# PWM.net
KiCad netlist of a schematic drawn in Altium Designer
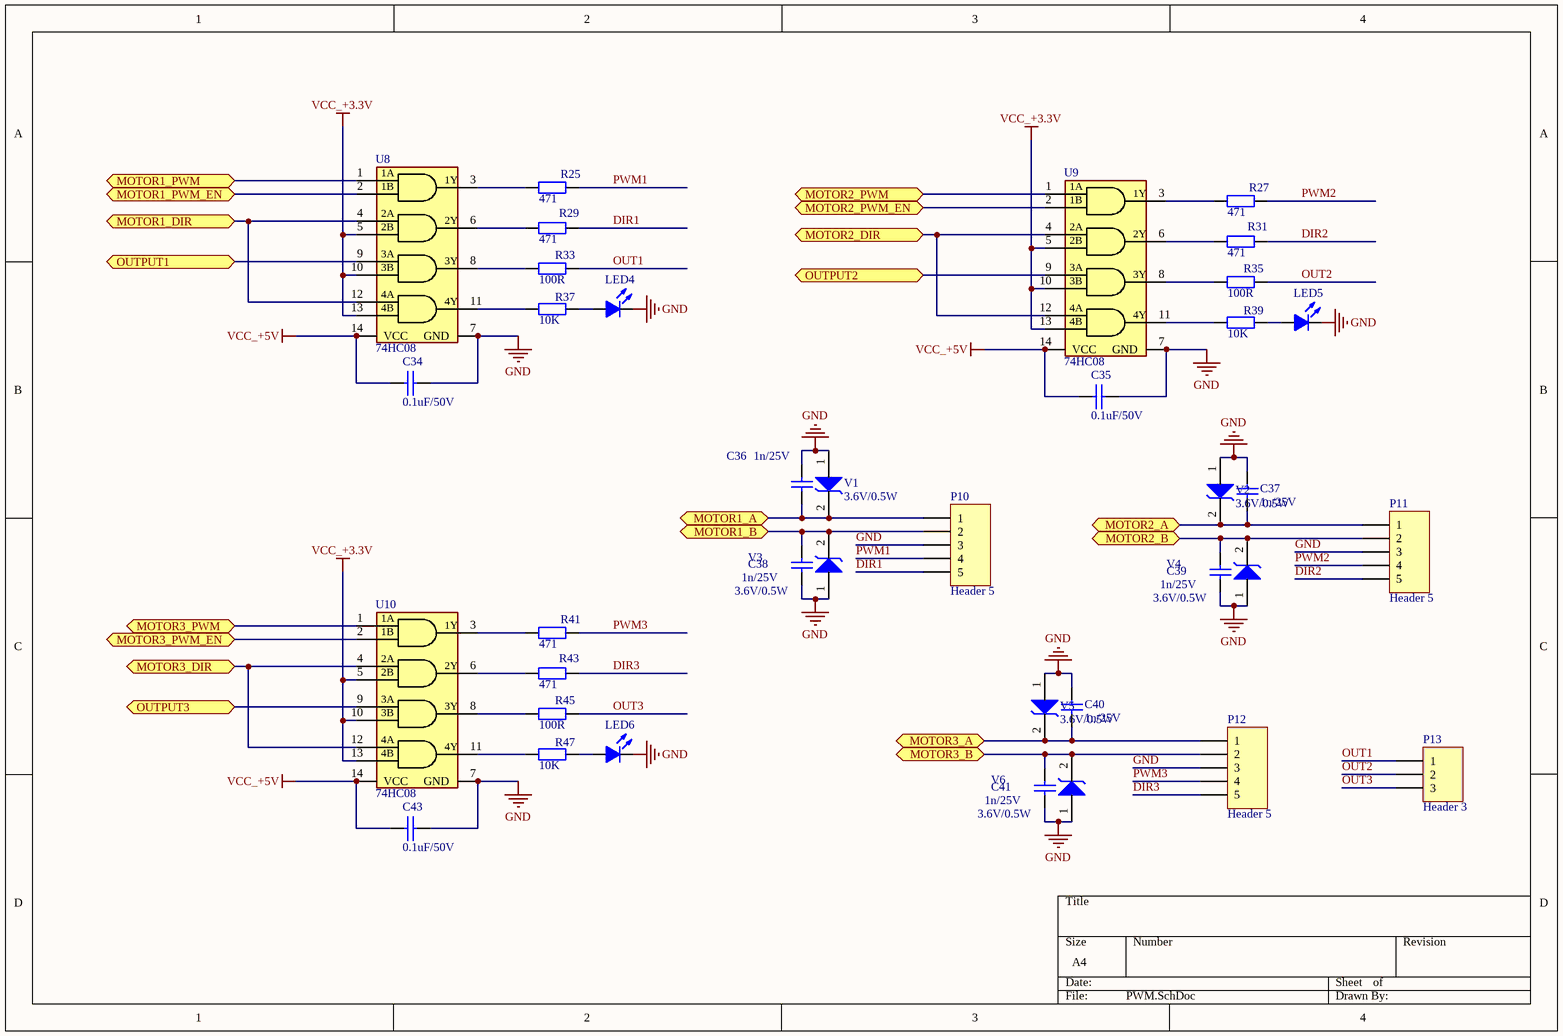
[diagram p0: PWM.SchDoc]

(export (version "E")
  (design (tool "Eeschema 10.0.6"))
  (components
    (comp (ref "C34") (value "0.1uF/50V") (footprint "0603C") (libsource (lib "*") (part "0603C")))
    (comp (ref "C35") (value "0.1uF/50V") (footprint "0603C") (libsource (lib "*") (part "0603C")))
    (comp (ref "C36")
      (value "1n/25V")
      (footprint "0603C")
      (description "Capacitor")
      (libsource (lib "*") (part "Cap"))
    )
    (comp (ref "C37")
      (value "1n/25V")
      (footprint "0603C")
      (description "Capacitor")
      (libsource (lib "*") (part "Cap"))
    )
    (comp (ref "C38")
      (value "1n/25V")
      (footprint "0603C")
      (description "Capacitor")
      (libsource (lib "*") (part "Cap"))
    )
    (comp (ref "C39")
      (value "1n/25V")
      (footprint "0603C")
      (description "Capacitor")
      (libsource (lib "*") (part "Cap"))
    )
    (comp (ref "C40")
      (value "1n/25V")
      (footprint "0603C")
      (description "Capacitor")
      (libsource (lib "*") (part "Cap"))
    )
    (comp (ref "C41")
      (value "1n/25V")
      (footprint "0603C")
      (description "Capacitor")
      (libsource (lib "*") (part "Cap"))
    )
    (comp (ref "C43") (value "0.1uF/50V") (footprint "0603C") (libsource (lib "*") (part "0603C")))
    (comp (ref "LED4")
      (value "LED")
      (footprint "LED-0603")
      (description "Typical INFRARED GaAs LED")
      (fields (field (name "PUBLISHER") "Altium Limited"))
      (libsource (lib "Calf") (part "LED"))
    )
    (comp (ref "LED5")
      (value "LED")
      (footprint "LED-0603")
      (description "Typical INFRARED GaAs LED")
      (fields (field (name "PUBLISHER") "Altium Limited"))
      (libsource (lib "Calf") (part "LED"))
    )
    (comp (ref "LED6")
      (value "LED")
      (footprint "LED-0603")
      (description "Typical INFRARED GaAs LED")
      (fields (field (name "PUBLISHER") "Altium Limited"))
      (libsource (lib "Calf") (part "LED"))
    )
    (comp (ref "P10")
      (value "Header 5")
      (footprint "HT396")
      (description "Header, 5-Pin")
      (fields (field (name "PUBLISHER") "Altium Limited"))
      (libsource (lib "Miscellaneous Connectors") (part "Header 5"))
    )
    (comp (ref "P11")
      (value "Header 5")
      (footprint "HT396")
      (description "Header, 5-Pin")
      (fields (field (name "PUBLISHER") "Altium Limited"))
      (libsource (lib "Miscellaneous Connectors") (part "Header 5"))
    )
    (comp (ref "P12")
      (value "Header 5")
      (footprint "HT396")
      (description "Header, 5-Pin")
      (fields (field (name "PUBLISHER") "Altium Limited"))
      (libsource (lib "Miscellaneous Connectors") (part "Header 5"))
    )
    (comp (ref "P13")
      (value "Header 3")
      (footprint "HT396  3P")
      (description "Header, 3-Pin")
      (fields (field (name "PUBLISHER") "Altium Limited"))
      (libsource (lib "Miscellaneous Connectors") (part "Header 3"))
    )
    (comp (ref "R25") (value "471") (footprint "0603R") (libsource (lib "*") (part "0603R")))
    (comp (ref "R27") (value "471") (footprint "0603R") (libsource (lib "*") (part "0603R")))
    (comp (ref "R29") (value "471") (footprint "0603R") (libsource (lib "*") (part "0603R")))
    (comp (ref "R31") (value "471") (footprint "0603R") (libsource (lib "*") (part "0603R")))
    (comp (ref "R33") (value "100R") (footprint "0603R") (libsource (lib "*") (part "0603R")))
    (comp (ref "R35") (value "100R") (footprint "0603R") (libsource (lib "*") (part "0603R")))
    (comp (ref "R37") (value "10K") (footprint "0603R") (libsource (lib "*") (part "0603R")))
    (comp (ref "R39") (value "10K") (footprint "0603R") (libsource (lib "*") (part "0603R")))
    (comp (ref "R41") (value "471") (footprint "0603R") (libsource (lib "*") (part "0603R")))
    (comp (ref "R43") (value "471") (footprint "0603R") (libsource (lib "*") (part "0603R")))
    (comp (ref "R45") (value "100R") (footprint "0603R") (libsource (lib "*") (part "0603R")))
    (comp (ref "R47") (value "10K") (footprint "0603R") (libsource (lib "*") (part "0603R")))
    (comp (ref "U8")
      (value "74HC08")
      (footprint "SOP14")
      (description "Quad 2-input NAND gate")
      (libsource (lib "Schlib") (part "74HC08"))
    )
    (comp (ref "U9")
      (value "74HC08")
      (footprint "SOP14")
      (description "Quad 2-input NAND gate")
      (libsource (lib "Schlib") (part "74HC08"))
    )
    (comp (ref "U10")
      (value "74HC08")
      (footprint "SOP14")
      (description "Quad 2-input NAND gate")
      (libsource (lib "Schlib") (part "74HC08"))
    )
    (comp (ref "V1")
      (value "3.6V/0.5W")
      (footprint "1206D")
      (description "DIODE SCHOTTKY")
      (libsource (lib "*") (part "DIODE-SCHOTTKY"))
    )
    (comp (ref "V2")
      (value "3.6V/0.5W")
      (footprint "1206D")
      (description "DIODE SCHOTTKY")
      (libsource (lib "*") (part "DIODE-SCHOTTKY"))
    )
    (comp (ref "V3")
      (value "3.6V/0.5W")
      (footprint "1206D")
      (description "DIODE SCHOTTKY")
      (libsource (lib "*") (part "DIODE-SCHOTTKY"))
    )
    (comp (ref "V4")
      (value "3.6V/0.5W")
      (footprint "1206D")
      (description "DIODE SCHOTTKY")
      (libsource (lib "*") (part "DIODE-SCHOTTKY"))
    )
    (comp (ref "V5")
      (value "3.6V/0.5W")
      (footprint "1206D")
      (description "DIODE SCHOTTKY")
      (libsource (lib "*") (part "DIODE-SCHOTTKY"))
    )
    (comp (ref "V6")
      (value "3.6V/0.5W")
      (footprint "1206D")
      (description "DIODE SCHOTTKY")
      (libsource (lib "*") (part "DIODE-SCHOTTKY"))
    )
  )
  (nets
    (net (code "1") (name "/DIR1") (class "Default")
      (node (ref "P10") (pin "5") (pinfunction "5_5") (pintype "passive"))
      (node (ref "R29") (pin "1") (pinfunction "1_1") (pintype "passive"))
    )
    (net (code "2") (name "/DIR2") (class "Default")
      (node (ref "P11") (pin "5") (pinfunction "5_5") (pintype "passive"))
      (node (ref "R31") (pin "1") (pinfunction "1_1") (pintype "passive"))
    )
    (net (code "3") (name "/DIR3") (class "Default")
      (node (ref "P12") (pin "5") (pinfunction "5_5") (pintype "passive"))
      (node (ref "R43") (pin "1") (pinfunction "1_1") (pintype "passive"))
    )
    (net (code "4") (name "/MOTOR1_A") (class "Default")
      (node (ref "C36") (pin "1") (pinfunction "1_1") (pintype "passive"))
      (node (ref "P10") (pin "1") (pinfunction "1_1") (pintype "passive"))
      (node (ref "V1") (pin "2") (pinfunction "2_2") (pintype "passive"))
    )
    (net (code "5") (name "/MOTOR1_B") (class "Default")
      (node (ref "C38") (pin "2") (pinfunction "2_2") (pintype "passive"))
      (node (ref "P10") (pin "2") (pinfunction "2_2") (pintype "passive"))
      (node (ref "V3") (pin "2") (pinfunction "2_2") (pintype "passive"))
    )
    (net (code "6") (name "/MOTOR1_DIR") (class "Default")
      (node (ref "U8") (pin "12") (pintype "passive"))
      (node (ref "U8") (pin "4") (pintype "passive"))
    )
    (net (code "7") (name "/MOTOR1_PWM") (class "Default")
      (node (ref "U8") (pin "1") (pinfunction "1A_1") (pintype "passive"))
    )
    (net (code "8") (name "/MOTOR1_PWM_EN") (class "Default")
      (node (ref "U8") (pin "2") (pinfunction "1B_2") (pintype "passive"))
    )
    (net (code "9") (name "/MOTOR2_A") (class "Default")
      (node (ref "C37") (pin "2") (pinfunction "2_2") (pintype "passive"))
      (node (ref "P11") (pin "1") (pinfunction "1_1") (pintype "passive"))
      (node (ref "V2") (pin "2") (pinfunction "2_2") (pintype "passive"))
    )
    (net (code "10") (name "/MOTOR2_B") (class "Default")
      (node (ref "C39") (pin "2") (pinfunction "2_2") (pintype "passive"))
      (node (ref "P11") (pin "2") (pinfunction "2_2") (pintype "passive"))
      (node (ref "V4") (pin "2") (pinfunction "2_2") (pintype "passive"))
    )
    (net (code "11") (name "/MOTOR2_DIR") (class "Default")
      (node (ref "U9") (pin "12") (pintype "passive"))
      (node (ref "U9") (pin "4") (pintype "passive"))
    )
    (net (code "12") (name "/MOTOR2_PWM") (class "Default")
      (node (ref "U9") (pin "1") (pinfunction "1A_1") (pintype "passive"))
    )
    (net (code "13") (name "/MOTOR2_PWM_EN") (class "Default")
      (node (ref "U9") (pin "2") (pinfunction "1B_2") (pintype "passive"))
    )
    (net (code "14") (name "/MOTOR3_A") (class "Default")
      (node (ref "C40") (pin "2") (pinfunction "2_2") (pintype "passive"))
      (node (ref "P12") (pin "1") (pinfunction "1_1") (pintype "passive"))
      (node (ref "V5") (pin "2") (pinfunction "2_2") (pintype "passive"))
    )
    (net (code "15") (name "/MOTOR3_B") (class "Default")
      (node (ref "C41") (pin "2") (pinfunction "2_2") (pintype "passive"))
      (node (ref "P12") (pin "2") (pinfunction "2_2") (pintype "passive"))
      (node (ref "V6") (pin "2") (pinfunction "2_2") (pintype "passive"))
    )
    (net (code "16") (name "/MOTOR3_DIR") (class "Default")
      (node (ref "U10") (pin "12") (pintype "passive"))
      (node (ref "U10") (pin "4") (pintype "passive"))
    )
    (net (code "17") (name "/MOTOR3_PWM") (class "Default")
      (node (ref "U10") (pin "1") (pinfunction "1A_1") (pintype "passive"))
    )
    (net (code "18") (name "/MOTOR3_PWM_EN") (class "Default")
      (node (ref "U10") (pin "2") (pinfunction "1B_2") (pintype "passive"))
    )
    (net (code "19") (name "/OUT1") (class "Default")
      (node (ref "P13") (pin "1") (pinfunction "1_1") (pintype "passive"))
      (node (ref "R33") (pin "1") (pinfunction "1_1") (pintype "passive"))
    )
    (net (code "20") (name "/OUT2") (class "Default")
      (node (ref "P13") (pin "2") (pinfunction "2_2") (pintype "passive"))
      (node (ref "R35") (pin "1") (pinfunction "1_1") (pintype "passive"))
    )
    (net (code "21") (name "/OUT3") (class "Default")
      (node (ref "P13") (pin "3") (pinfunction "3_3") (pintype "passive"))
      (node (ref "R45") (pin "1") (pinfunction "1_1") (pintype "passive"))
    )
    (net (code "22") (name "/OUTPUT1") (class "Default") (node (ref "U8") (pin "9") (pintype "passive")))
    (net (code "23") (name "/OUTPUT2") (class "Default") (node (ref "U9") (pin "9") (pintype "passive")))
    (net (code "24") (name "/OUTPUT3") (class "Default") (node (ref "U10") (pin "9") (pintype "passive")))
    (net (code "25") (name "/PWM1") (class "Default")
      (node (ref "P10") (pin "4") (pinfunction "4_4") (pintype "passive"))
      (node (ref "R25") (pin "1") (pinfunction "1_1") (pintype "passive"))
    )
    (net (code "26") (name "/PWM2") (class "Default")
      (node (ref "P11") (pin "4") (pinfunction "4_4") (pintype "passive"))
      (node (ref "R27") (pin "1") (pinfunction "1_1") (pintype "passive"))
    )
    (net (code "27") (name "/PWM3") (class "Default")
      (node (ref "P12") (pin "4") (pinfunction "4_4") (pintype "passive"))
      (node (ref "R41") (pin "1") (pinfunction "1_1") (pintype "passive"))
    )
    (net (code "28") (name "GND") (class "Default")
      (node (ref "C34") (pin "2") (pintype "passive"))
      (node (ref "C35") (pin "2") (pintype "passive"))
      (node (ref "C36") (pin "2") (pinfunction "2_2") (pintype "passive"))
      (node (ref "C37") (pin "1") (pinfunction "1_1") (pintype "passive"))
      (node (ref "C38") (pin "1") (pinfunction "1_1") (pintype "passive"))
      (node (ref "C39") (pin "1") (pinfunction "1_1") (pintype "passive"))
      (node (ref "C40") (pin "1") (pinfunction "1_1") (pintype "passive"))
      (node (ref "C41") (pin "1") (pinfunction "1_1") (pintype "passive"))
      (node (ref "C43") (pin "2") (pintype "passive"))
      (node (ref "LED4") (pin "2") (pinfunction "K_2") (pintype "passive"))
      (node (ref "LED5") (pin "2") (pinfunction "K_2") (pintype "passive"))
      (node (ref "LED6") (pin "2") (pinfunction "K_2") (pintype "passive"))
      (node (ref "P10") (pin "3") (pinfunction "3_3") (pintype "passive"))
      (node (ref "P11") (pin "3") (pinfunction "3_3") (pintype "passive"))
      (node (ref "P12") (pin "3") (pinfunction "3_3") (pintype "passive"))
      (node (ref "U10") (pin "7") (pinfunction "GND_7") (pintype "passive"))
      (node (ref "U8") (pin "7") (pinfunction "GND_7") (pintype "passive"))
      (node (ref "U9") (pin "7") (pinfunction "GND_7") (pintype "passive"))
      (node (ref "V1") (pin "1") (pinfunction "1_1") (pintype "passive"))
      (node (ref "V2") (pin "1") (pinfunction "1_1") (pintype "passive"))
      (node (ref "V3") (pin "1") (pinfunction "1_1") (pintype "passive"))
      (node (ref "V4") (pin "1") (pinfunction "1_1") (pintype "passive"))
      (node (ref "V5") (pin "1") (pinfunction "1_1") (pintype "passive"))
      (node (ref "V6") (pin "1") (pinfunction "1_1") (pintype "passive"))
    )
    (net (code "29") (name "Net-(LED4-A)") (class "Default")
      (node (ref "LED4") (pin "1") (pinfunction "A_1") (pintype "passive"))
      (node (ref "R37") (pin "1") (pinfunction "1_1") (pintype "passive"))
    )
    (net (code "30") (name "Net-(LED5-A)") (class "Default")
      (node (ref "LED5") (pin "1") (pinfunction "A_1") (pintype "passive"))
      (node (ref "R39") (pin "1") (pinfunction "1_1") (pintype "passive"))
    )
    (net (code "31") (name "Net-(LED6-A)") (class "Default")
      (node (ref "LED6") (pin "1") (pinfunction "A_1") (pintype "passive"))
      (node (ref "R47") (pin "1") (pinfunction "1_1") (pintype "passive"))
    )
    (net (code "32") (name "Net-(R29-Pad2)") (class "Default")
      (node (ref "R29") (pin "2") (pinfunction "2_2") (pintype "passive"))
      (node (ref "U8") (pin "6") (pintype "passive"))
    )
    (net (code "33") (name "Net-(R31-Pad2)") (class "Default")
      (node (ref "R31") (pin "2") (pinfunction "2_2") (pintype "passive"))
      (node (ref "U9") (pin "6") (pintype "passive"))
    )
    (net (code "34") (name "Net-(R33-Pad2)") (class "Default")
      (node (ref "R33") (pin "2") (pinfunction "2_2") (pintype "passive"))
      (node (ref "U8") (pin "8") (pintype "passive"))
    )
    (net (code "35") (name "Net-(R35-Pad2)") (class "Default")
      (node (ref "R35") (pin "2") (pinfunction "2_2") (pintype "passive"))
      (node (ref "U9") (pin "8") (pintype "passive"))
    )
    (net (code "36") (name "Net-(R37-Pad2)") (class "Default")
      (node (ref "R37") (pin "2") (pinfunction "2_2") (pintype "passive"))
      (node (ref "U8") (pin "11") (pintype "passive"))
    )
    (net (code "37") (name "Net-(R39-Pad2)") (class "Default")
      (node (ref "R39") (pin "2") (pinfunction "2_2") (pintype "passive"))
      (node (ref "U9") (pin "11") (pintype "passive"))
    )
    (net (code "38") (name "Net-(R43-Pad2)") (class "Default")
      (node (ref "R43") (pin "2") (pinfunction "2_2") (pintype "passive"))
      (node (ref "U10") (pin "6") (pintype "passive"))
    )
    (net (code "39") (name "Net-(R45-Pad2)") (class "Default")
      (node (ref "R45") (pin "2") (pinfunction "2_2") (pintype "passive"))
      (node (ref "U10") (pin "8") (pintype "passive"))
    )
    (net (code "40") (name "Net-(R47-Pad2)") (class "Default")
      (node (ref "R47") (pin "2") (pinfunction "2_2") (pintype "passive"))
      (node (ref "U10") (pin "11") (pintype "passive"))
    )
    (net (code "41") (name "Net-(U8-1Y)") (class "Default")
      (node (ref "R25") (pin "2") (pinfunction "2_2") (pintype "passive"))
      (node (ref "U8") (pin "3") (pinfunction "1Y_3") (pintype "passive"))
    )
    (net (code "42") (name "Net-(U9-1Y)") (class "Default")
      (node (ref "R27") (pin "2") (pinfunction "2_2") (pintype "passive"))
      (node (ref "U9") (pin "3") (pinfunction "1Y_3") (pintype "passive"))
    )
    (net (code "43") (name "Net-(U10-1Y)") (class "Default")
      (node (ref "R41") (pin "2") (pinfunction "2_2") (pintype "passive"))
      (node (ref "U10") (pin "3") (pinfunction "1Y_3") (pintype "passive"))
    )
    (net (code "44") (name "VCC_+3.3V") (class "Default")
      (node (ref "U10") (pin "10") (pinfunction "1B_10") (pintype "passive"))
      (node (ref "U10") (pin "13") (pintype "passive"))
      (node (ref "U10") (pin "5") (pintype "passive"))
      (node (ref "U8") (pin "10") (pinfunction "1B_10") (pintype "passive"))
      (node (ref "U8") (pin "13") (pintype "passive"))
      (node (ref "U8") (pin "5") (pintype "passive"))
      (node (ref "U9") (pin "10") (pinfunction "1B_10") (pintype "passive"))
      (node (ref "U9") (pin "13") (pintype "passive"))
      (node (ref "U9") (pin "5") (pintype "passive"))
    )
    (net (code "45") (name "VCC_+5V") (class "Default")
      (node (ref "C34") (pin "1") (pintype "passive"))
      (node (ref "C35") (pin "1") (pintype "passive"))
      (node (ref "C43") (pin "1") (pintype "passive"))
      (node (ref "U10") (pin "14") (pinfunction "VCC_14") (pintype "passive"))
      (node (ref "U8") (pin "14") (pinfunction "VCC_14") (pintype "passive"))
      (node (ref "U9") (pin "14") (pinfunction "VCC_14") (pintype "passive"))
    )
  )
)
